# pimotor.net
KiCad netlist of a schematic drawn in EAGLE
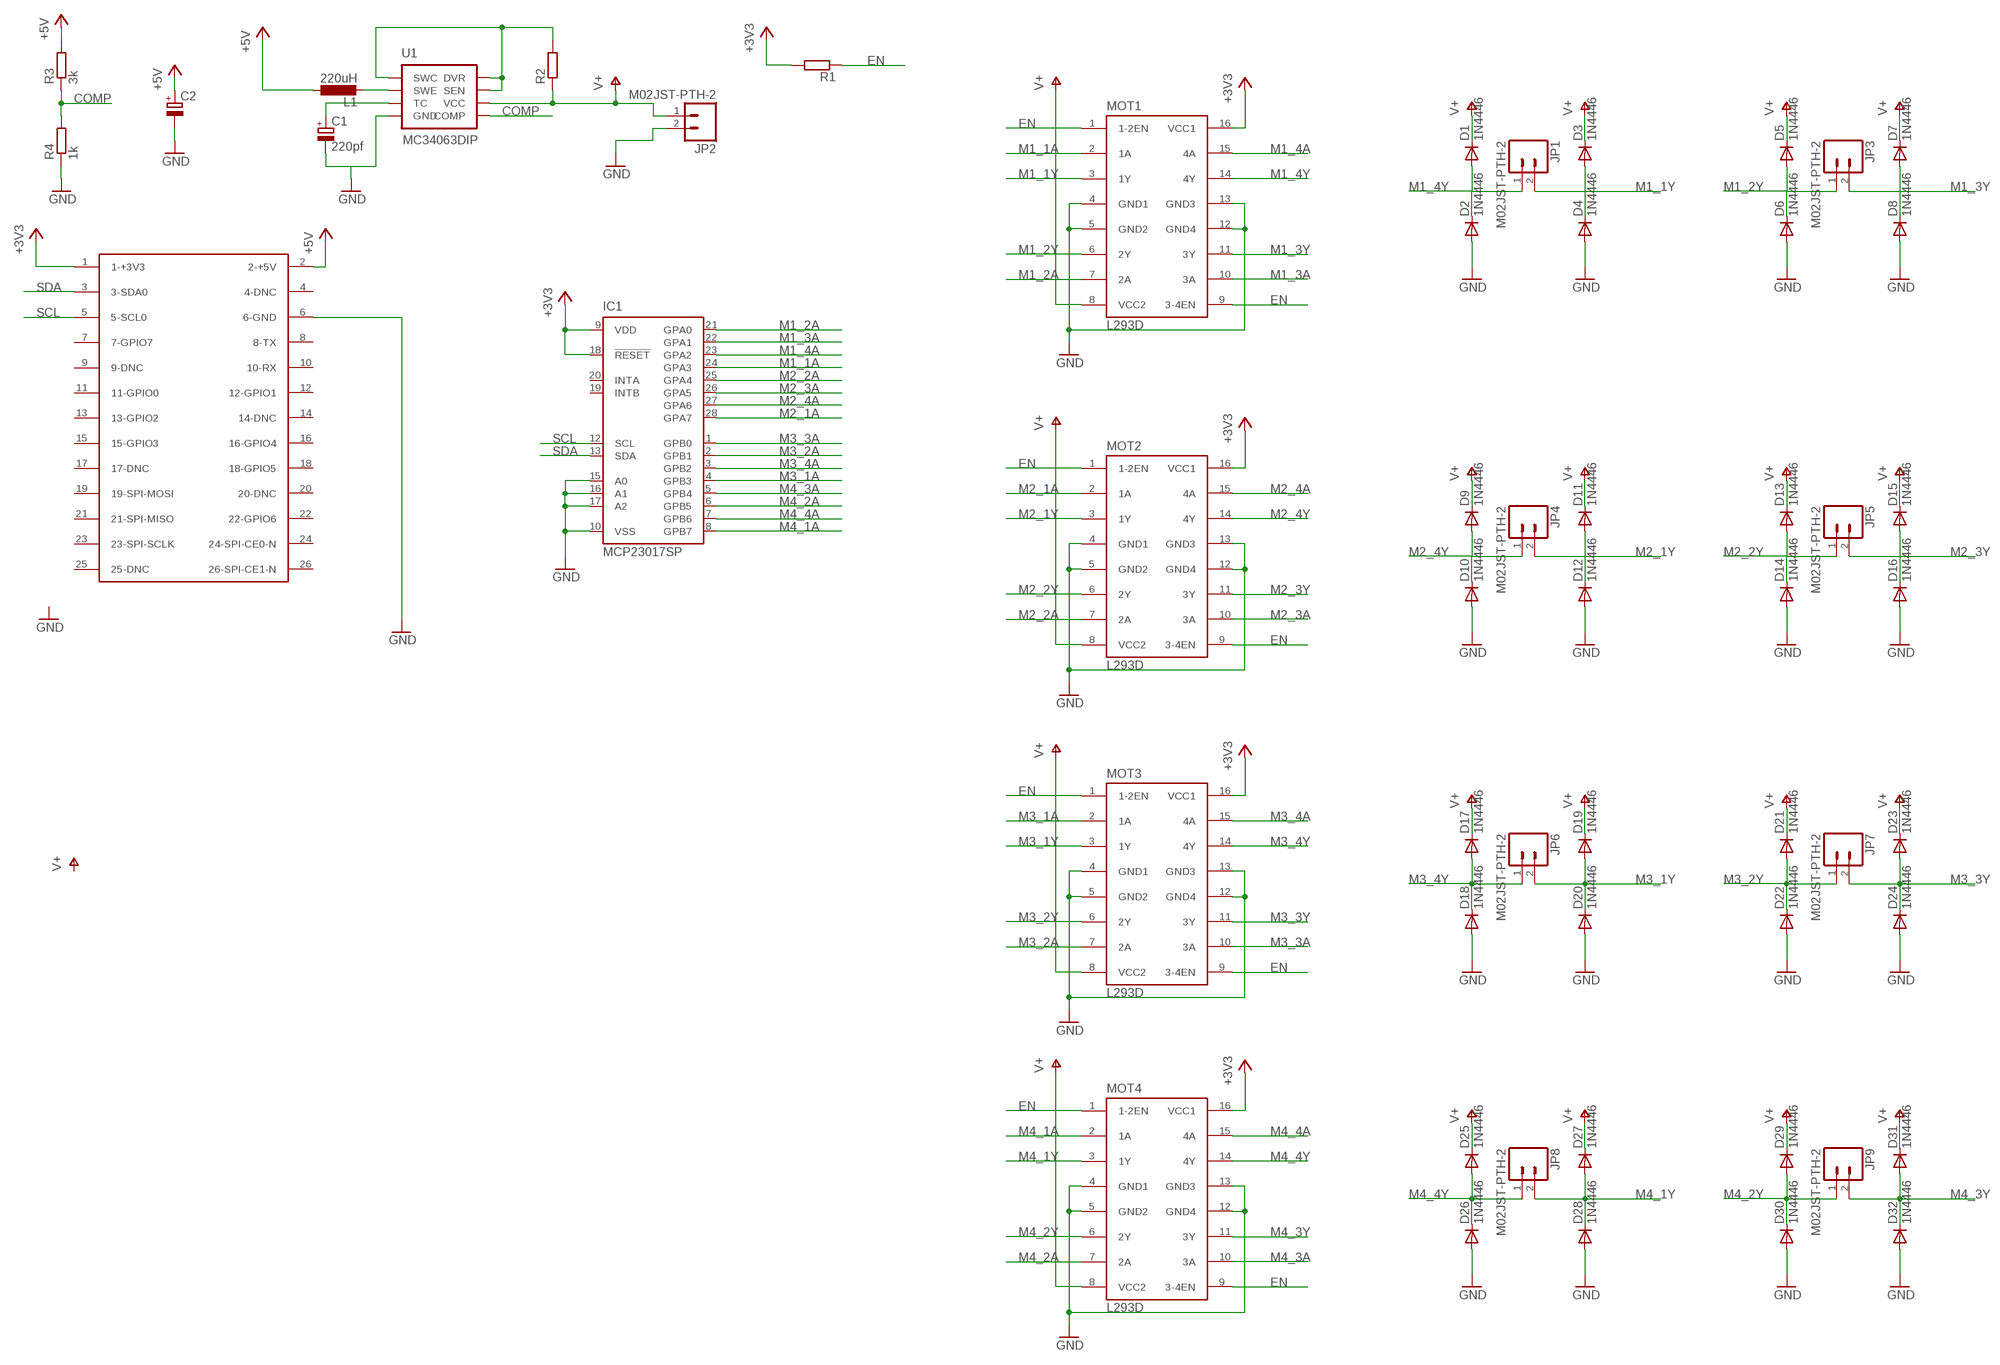
[diagram p0: schematic, sheet 1]

(export (version "E")
  (design (tool "Eeschema 10.0.6"))
  (components
    (comp (ref "C1")
      (value "220pf")
      (footprint "eagle-import:E3,5-8")
      (libsource (lib "eagle-import") (part "CPOL-EUE3.5-8"))
    )
    (comp (ref "C2")
      (value "CPOL-EUE3.5-8")
      (footprint "eagle-import:E3,5-8")
      (libsource (lib "eagle-import") (part "CPOL-EUE3.5-8"))
    )
    (comp (ref "D1")
      (value "1N4446")
      (footprint "eagle-import:DO35-10")
      (libsource (lib "eagle-import") (part "1N4446"))
    )
    (comp (ref "D2")
      (value "1N4446")
      (footprint "eagle-import:DO35-10")
      (libsource (lib "eagle-import") (part "1N4446"))
    )
    (comp (ref "D3")
      (value "1N4446")
      (footprint "eagle-import:DO35-10")
      (libsource (lib "eagle-import") (part "1N4446"))
    )
    (comp (ref "D4")
      (value "1N4446")
      (footprint "eagle-import:DO35-10")
      (libsource (lib "eagle-import") (part "1N4446"))
    )
    (comp (ref "D5")
      (value "1N4446")
      (footprint "eagle-import:DO35-10")
      (libsource (lib "eagle-import") (part "1N4446"))
    )
    (comp (ref "D6")
      (value "1N4446")
      (footprint "eagle-import:DO35-10")
      (libsource (lib "eagle-import") (part "1N4446"))
    )
    (comp (ref "D7")
      (value "1N4446")
      (footprint "eagle-import:DO35-10")
      (libsource (lib "eagle-import") (part "1N4446"))
    )
    (comp (ref "D8")
      (value "1N4446")
      (footprint "eagle-import:DO35-10")
      (libsource (lib "eagle-import") (part "1N4446"))
    )
    (comp (ref "D9")
      (value "1N4446")
      (footprint "eagle-import:DO35-10")
      (libsource (lib "eagle-import") (part "1N4446"))
    )
    (comp (ref "D10")
      (value "1N4446")
      (footprint "eagle-import:DO35-10")
      (libsource (lib "eagle-import") (part "1N4446"))
    )
    (comp (ref "D11")
      (value "1N4446")
      (footprint "eagle-import:DO35-10")
      (libsource (lib "eagle-import") (part "1N4446"))
    )
    (comp (ref "D12")
      (value "1N4446")
      (footprint "eagle-import:DO35-10")
      (libsource (lib "eagle-import") (part "1N4446"))
    )
    (comp (ref "D13")
      (value "1N4446")
      (footprint "eagle-import:DO35-10")
      (libsource (lib "eagle-import") (part "1N4446"))
    )
    (comp (ref "D14")
      (value "1N4446")
      (footprint "eagle-import:DO35-10")
      (libsource (lib "eagle-import") (part "1N4446"))
    )
    (comp (ref "D15")
      (value "1N4446")
      (footprint "eagle-import:DO35-10")
      (libsource (lib "eagle-import") (part "1N4446"))
    )
    (comp (ref "D16")
      (value "1N4446")
      (footprint "eagle-import:DO35-10")
      (libsource (lib "eagle-import") (part "1N4446"))
    )
    (comp (ref "D17")
      (value "1N4446")
      (footprint "eagle-import:DO35-10")
      (libsource (lib "eagle-import") (part "1N4446"))
    )
    (comp (ref "D18")
      (value "1N4446")
      (footprint "eagle-import:DO35-10")
      (libsource (lib "eagle-import") (part "1N4446"))
    )
    (comp (ref "D19")
      (value "1N4446")
      (footprint "eagle-import:DO35-10")
      (libsource (lib "eagle-import") (part "1N4446"))
    )
    (comp (ref "D20")
      (value "1N4446")
      (footprint "eagle-import:DO35-10")
      (libsource (lib "eagle-import") (part "1N4446"))
    )
    (comp (ref "D21")
      (value "1N4446")
      (footprint "eagle-import:DO35-10")
      (libsource (lib "eagle-import") (part "1N4446"))
    )
    (comp (ref "D22")
      (value "1N4446")
      (footprint "eagle-import:DO35-10")
      (libsource (lib "eagle-import") (part "1N4446"))
    )
    (comp (ref "D23")
      (value "1N4446")
      (footprint "eagle-import:DO35-10")
      (libsource (lib "eagle-import") (part "1N4446"))
    )
    (comp (ref "D24")
      (value "1N4446")
      (footprint "eagle-import:DO35-10")
      (libsource (lib "eagle-import") (part "1N4446"))
    )
    (comp (ref "D25")
      (value "1N4446")
      (footprint "eagle-import:DO35-10")
      (libsource (lib "eagle-import") (part "1N4446"))
    )
    (comp (ref "D26")
      (value "1N4446")
      (footprint "eagle-import:DO35-10")
      (libsource (lib "eagle-import") (part "1N4446"))
    )
    (comp (ref "D27")
      (value "1N4446")
      (footprint "eagle-import:DO35-10")
      (libsource (lib "eagle-import") (part "1N4446"))
    )
    (comp (ref "D28")
      (value "1N4446")
      (footprint "eagle-import:DO35-10")
      (libsource (lib "eagle-import") (part "1N4446"))
    )
    (comp (ref "D29")
      (value "1N4446")
      (footprint "eagle-import:DO35-10")
      (libsource (lib "eagle-import") (part "1N4446"))
    )
    (comp (ref "D30")
      (value "1N4446")
      (footprint "eagle-import:DO35-10")
      (libsource (lib "eagle-import") (part "1N4446"))
    )
    (comp (ref "D31")
      (value "1N4446")
      (footprint "eagle-import:DO35-10")
      (libsource (lib "eagle-import") (part "1N4446"))
    )
    (comp (ref "D32")
      (value "1N4446")
      (footprint "eagle-import:DO35-10")
      (libsource (lib "eagle-import") (part "1N4446"))
    )
    (comp (ref "IC1")
      (value "MCP23017SP")
      (footprint "eagle-import:DIL28-3")
      (libsource (lib "eagle-import") (part "MCP23017SP"))
    )
    (comp (ref "JP1")
      (value "M02JST-PTH-2")
      (footprint "eagle-import:JST-2-PTH")
      (libsource (lib "eagle-import") (part "M02JST-PTH-2"))
    )
    (comp (ref "JP2")
      (value "M02JST-PTH-2")
      (footprint "eagle-import:JST-2-PTH")
      (libsource (lib "eagle-import") (part "M02JST-PTH-2"))
    )
    (comp (ref "JP3")
      (value "M02JST-PTH-2")
      (footprint "eagle-import:JST-2-PTH")
      (libsource (lib "eagle-import") (part "M02JST-PTH-2"))
    )
    (comp (ref "JP4")
      (value "M02JST-PTH-2")
      (footprint "eagle-import:JST-2-PTH")
      (libsource (lib "eagle-import") (part "M02JST-PTH-2"))
    )
    (comp (ref "JP5")
      (value "M02JST-PTH-2")
      (footprint "eagle-import:JST-2-PTH")
      (libsource (lib "eagle-import") (part "M02JST-PTH-2"))
    )
    (comp (ref "JP6")
      (value "M02JST-PTH-2")
      (footprint "eagle-import:JST-2-PTH")
      (libsource (lib "eagle-import") (part "M02JST-PTH-2"))
    )
    (comp (ref "JP7")
      (value "M02JST-PTH-2")
      (footprint "eagle-import:JST-2-PTH")
      (libsource (lib "eagle-import") (part "M02JST-PTH-2"))
    )
    (comp (ref "JP8")
      (value "M02JST-PTH-2")
      (footprint "eagle-import:JST-2-PTH")
      (libsource (lib "eagle-import") (part "M02JST-PTH-2"))
    )
    (comp (ref "JP9")
      (value "M02JST-PTH-2")
      (footprint "eagle-import:JST-2-PTH")
      (libsource (lib "eagle-import") (part "M02JST-PTH-2"))
    )
    (comp (ref "L1")
      (value "220uH")
      (footprint "eagle-import:0204_7")
      (libsource (lib "eagle-import") (part "L-EU0204/7"))
    )
    (comp (ref "MOT1")
      (value "L293D")
      (footprint "eagle-import:DIL16")
      (libsource (lib "eagle-import") (part "L293D"))
    )
    (comp (ref "MOT2")
      (value "L293D")
      (footprint "eagle-import:DIL16")
      (libsource (lib "eagle-import") (part "L293D"))
    )
    (comp (ref "MOT3")
      (value "L293D")
      (footprint "eagle-import:DIL16")
      (libsource (lib "eagle-import") (part "L293D"))
    )
    (comp (ref "MOT4")
      (value "L293D")
      (footprint "eagle-import:DIL16")
      (libsource (lib "eagle-import") (part "L293D"))
    )
    (comp (ref "R1")
      (value "R-EU_0204/7")
      (footprint "eagle-import:0204_7")
      (libsource (lib "eagle-import") (part "R-EU_0204/7"))
    )
    (comp (ref "R2")
      (value "R-EU_0204/7")
      (footprint "eagle-import:0204_7")
      (libsource (lib "eagle-import") (part "R-EU_0204/7"))
    )
    (comp (ref "R3")
      (value "3k")
      (footprint "eagle-import:0204_7")
      (libsource (lib "eagle-import") (part "R-EU_0204/7"))
    )
    (comp (ref "R4")
      (value "1k")
      (footprint "eagle-import:0204_7")
      (libsource (lib "eagle-import") (part "R-EU_0204/7"))
    )
    (comp (ref "U$1")
      (value "RASPBERRY-PI")
      (footprint "eagle-import:RASPBERRY-PI")
      (libsource (lib "eagle-import") (part "RASPBERRY-PI"))
    )
    (comp (ref "U1")
      (value "MC34063DIP")
      (footprint "eagle-import:DIP-08")
      (libsource (lib "eagle-import") (part "MC34063DIP"))
    )
  )
  (nets
    (net (code "1") (name "+3V3") (class "Default")
      (node (ref "IC1") (pin "18") (pinfunction "~{RESET}_18") (pintype "input"))
      (node (ref "IC1") (pin "9") (pinfunction "VDD_9") (pintype "power_in"))
      (node (ref "MOT1") (pin "16") (pinfunction "VCC1_16") (pintype "power_in"))
      (node (ref "MOT2") (pin "16") (pinfunction "VCC1_16") (pintype "power_in"))
      (node (ref "MOT3") (pin "16") (pinfunction "VCC1_16") (pintype "power_in"))
      (node (ref "MOT4") (pin "16") (pinfunction "VCC1_16") (pintype "power_in"))
      (node (ref "R1") (pin "2") (pinfunction "2_2") (pintype "passive"))
      (node (ref "U$1") (pin "1") (pinfunction "1-+3V3_1") (pintype "bidirectional"))
    )
    (net (code "2") (name "+5V") (class "Default")
      (node (ref "C2") (pin "+") (pinfunction "+_+") (pintype "passive"))
      (node (ref "L1") (pin "1") (pinfunction "1_1") (pintype "passive"))
      (node (ref "R3") (pin "2") (pinfunction "2_2") (pintype "passive"))
      (node (ref "U$1") (pin "2") (pinfunction "2-+5V_2") (pintype "bidirectional"))
    )
    (net (code "3") (name "/COMP") (class "Default")
      (node (ref "R3") (pin "1") (pinfunction "1_1") (pintype "passive"))
      (node (ref "R4") (pin "2") (pinfunction "2_2") (pintype "passive"))
      (node (ref "U1") (pin "5") (pinfunction "COMP_5") (pintype "bidirectional"))
    )
    (net (code "4") (name "/EN") (class "Default")
      (node (ref "MOT1") (pin "1") (pinfunction "1-2EN_1") (pintype "input"))
      (node (ref "MOT1") (pin "9") (pinfunction "3-4EN_9") (pintype "input"))
      (node (ref "MOT2") (pin "1") (pinfunction "1-2EN_1") (pintype "input"))
      (node (ref "MOT2") (pin "9") (pinfunction "3-4EN_9") (pintype "input"))
      (node (ref "MOT3") (pin "1") (pinfunction "1-2EN_1") (pintype "input"))
      (node (ref "MOT3") (pin "9") (pinfunction "3-4EN_9") (pintype "input"))
      (node (ref "MOT4") (pin "1") (pinfunction "1-2EN_1") (pintype "input"))
      (node (ref "MOT4") (pin "9") (pinfunction "3-4EN_9") (pintype "input"))
      (node (ref "R1") (pin "1") (pinfunction "1_1") (pintype "passive"))
    )
    (net (code "5") (name "/M1_1A") (class "Default")
      (node (ref "IC1") (pin "24") (pinfunction "GPA3_24") (pintype "bidirectional"))
      (node (ref "MOT1") (pin "2") (pinfunction "1A_2") (pintype "input"))
    )
    (net (code "6") (name "/M1_1Y") (class "Default")
      (node (ref "D3") (pin "A") (pinfunction "A_A") (pintype "passive"))
      (node (ref "D4") (pin "C") (pinfunction "C_C") (pintype "passive"))
      (node (ref "JP1") (pin "2") (pinfunction "2_2") (pintype "passive"))
      (node (ref "MOT1") (pin "3") (pinfunction "1Y_3") (pintype "output"))
    )
    (net (code "7") (name "/M1_2A") (class "Default")
      (node (ref "IC1") (pin "21") (pinfunction "GPA0_21") (pintype "bidirectional"))
      (node (ref "MOT1") (pin "7") (pinfunction "2A_7") (pintype "input"))
    )
    (net (code "8") (name "/M1_2Y") (class "Default")
      (node (ref "D5") (pin "A") (pinfunction "A_A") (pintype "passive"))
      (node (ref "D6") (pin "C") (pinfunction "C_C") (pintype "passive"))
      (node (ref "JP3") (pin "1") (pinfunction "1_1") (pintype "passive"))
      (node (ref "MOT1") (pin "6") (pinfunction "2Y_6") (pintype "output"))
    )
    (net (code "9") (name "/M1_3A") (class "Default")
      (node (ref "IC1") (pin "22") (pinfunction "GPA1_22") (pintype "bidirectional"))
      (node (ref "MOT1") (pin "10") (pinfunction "3A_10") (pintype "input"))
    )
    (net (code "10") (name "/M1_3Y") (class "Default")
      (node (ref "D7") (pin "A") (pinfunction "A_A") (pintype "passive"))
      (node (ref "D8") (pin "C") (pinfunction "C_C") (pintype "passive"))
      (node (ref "JP3") (pin "2") (pinfunction "2_2") (pintype "passive"))
      (node (ref "MOT1") (pin "11") (pinfunction "3Y_11") (pintype "output"))
    )
    (net (code "11") (name "/M1_4A") (class "Default")
      (node (ref "IC1") (pin "23") (pinfunction "GPA2_23") (pintype "bidirectional"))
      (node (ref "MOT1") (pin "15") (pinfunction "4A_15") (pintype "input"))
    )
    (net (code "12") (name "/M1_4Y") (class "Default")
      (node (ref "D1") (pin "A") (pinfunction "A_A") (pintype "passive"))
      (node (ref "D2") (pin "C") (pinfunction "C_C") (pintype "passive"))
      (node (ref "JP1") (pin "1") (pinfunction "1_1") (pintype "passive"))
      (node (ref "MOT1") (pin "14") (pinfunction "4Y_14") (pintype "output"))
    )
    (net (code "13") (name "/M2_1A") (class "Default")
      (node (ref "IC1") (pin "28") (pinfunction "GPA7_28") (pintype "bidirectional"))
      (node (ref "MOT2") (pin "2") (pinfunction "1A_2") (pintype "input"))
    )
    (net (code "14") (name "/M2_1Y") (class "Default")
      (node (ref "D11") (pin "A") (pinfunction "A_A") (pintype "passive"))
      (node (ref "D12") (pin "C") (pinfunction "C_C") (pintype "passive"))
      (node (ref "JP4") (pin "2") (pinfunction "2_2") (pintype "passive"))
      (node (ref "MOT2") (pin "3") (pinfunction "1Y_3") (pintype "output"))
    )
    (net (code "15") (name "/M2_2A") (class "Default")
      (node (ref "IC1") (pin "25") (pinfunction "GPA4_25") (pintype "bidirectional"))
      (node (ref "MOT2") (pin "7") (pinfunction "2A_7") (pintype "input"))
    )
    (net (code "16") (name "/M2_2Y") (class "Default")
      (node (ref "D13") (pin "A") (pinfunction "A_A") (pintype "passive"))
      (node (ref "D14") (pin "C") (pinfunction "C_C") (pintype "passive"))
      (node (ref "JP5") (pin "1") (pinfunction "1_1") (pintype "passive"))
      (node (ref "MOT2") (pin "6") (pinfunction "2Y_6") (pintype "output"))
    )
    (net (code "17") (name "/M2_3A") (class "Default")
      (node (ref "IC1") (pin "26") (pinfunction "GPA5_26") (pintype "bidirectional"))
      (node (ref "MOT2") (pin "10") (pinfunction "3A_10") (pintype "input"))
    )
    (net (code "18") (name "/M2_3Y") (class "Default")
      (node (ref "D15") (pin "A") (pinfunction "A_A") (pintype "passive"))
      (node (ref "D16") (pin "C") (pinfunction "C_C") (pintype "passive"))
      (node (ref "JP5") (pin "2") (pinfunction "2_2") (pintype "passive"))
      (node (ref "MOT2") (pin "11") (pinfunction "3Y_11") (pintype "output"))
    )
    (net (code "19") (name "/M2_4A") (class "Default")
      (node (ref "IC1") (pin "27") (pinfunction "GPA6_27") (pintype "bidirectional"))
      (node (ref "MOT2") (pin "15") (pinfunction "4A_15") (pintype "input"))
    )
    (net (code "20") (name "/M2_4Y") (class "Default")
      (node (ref "D10") (pin "C") (pinfunction "C_C") (pintype "passive"))
      (node (ref "D9") (pin "A") (pinfunction "A_A") (pintype "passive"))
      (node (ref "JP4") (pin "1") (pinfunction "1_1") (pintype "passive"))
      (node (ref "MOT2") (pin "14") (pinfunction "4Y_14") (pintype "output"))
    )
    (net (code "21") (name "/M3_1A") (class "Default")
      (node (ref "IC1") (pin "4") (pinfunction "GPB3_4") (pintype "bidirectional"))
      (node (ref "MOT3") (pin "2") (pinfunction "1A_2") (pintype "input"))
    )
    (net (code "22") (name "/M3_1Y") (class "Default")
      (node (ref "D19") (pin "A") (pinfunction "A_A") (pintype "passive"))
      (node (ref "D20") (pin "C") (pinfunction "C_C") (pintype "passive"))
      (node (ref "JP6") (pin "2") (pinfunction "2_2") (pintype "passive"))
      (node (ref "MOT3") (pin "3") (pinfunction "1Y_3") (pintype "output"))
    )
    (net (code "23") (name "/M3_2A") (class "Default")
      (node (ref "IC1") (pin "2") (pinfunction "GPB1_2") (pintype "bidirectional"))
      (node (ref "MOT3") (pin "7") (pinfunction "2A_7") (pintype "input"))
    )
    (net (code "24") (name "/M3_2Y") (class "Default")
      (node (ref "D21") (pin "A") (pinfunction "A_A") (pintype "passive"))
      (node (ref "D22") (pin "C") (pinfunction "C_C") (pintype "passive"))
      (node (ref "JP7") (pin "1") (pinfunction "1_1") (pintype "passive"))
      (node (ref "MOT3") (pin "6") (pinfunction "2Y_6") (pintype "output"))
    )
    (net (code "25") (name "/M3_3A") (class "Default")
      (node (ref "IC1") (pin "1") (pinfunction "GPB0_1") (pintype "bidirectional"))
      (node (ref "MOT3") (pin "10") (pinfunction "3A_10") (pintype "input"))
    )
    (net (code "26") (name "/M3_3Y") (class "Default")
      (node (ref "D23") (pin "A") (pinfunction "A_A") (pintype "passive"))
      (node (ref "D24") (pin "C") (pinfunction "C_C") (pintype "passive"))
      (node (ref "JP7") (pin "2") (pinfunction "2_2") (pintype "passive"))
      (node (ref "MOT3") (pin "11") (pinfunction "3Y_11") (pintype "output"))
    )
    (net (code "27") (name "/M3_4A") (class "Default")
      (node (ref "IC1") (pin "3") (pinfunction "GPB2_3") (pintype "bidirectional"))
      (node (ref "MOT3") (pin "15") (pinfunction "4A_15") (pintype "input"))
    )
    (net (code "28") (name "/M3_4Y") (class "Default")
      (node (ref "D17") (pin "A") (pinfunction "A_A") (pintype "passive"))
      (node (ref "D18") (pin "C") (pinfunction "C_C") (pintype "passive"))
      (node (ref "JP6") (pin "1") (pinfunction "1_1") (pintype "passive"))
      (node (ref "MOT3") (pin "14") (pinfunction "4Y_14") (pintype "output"))
    )
    (net (code "29") (name "/M4_1A") (class "Default")
      (node (ref "IC1") (pin "8") (pinfunction "GPB7_8") (pintype "bidirectional"))
      (node (ref "MOT4") (pin "2") (pinfunction "1A_2") (pintype "input"))
    )
    (net (code "30") (name "/M4_1Y") (class "Default")
      (node (ref "D27") (pin "A") (pinfunction "A_A") (pintype "passive"))
      (node (ref "D28") (pin "C") (pinfunction "C_C") (pintype "passive"))
      (node (ref "JP8") (pin "2") (pinfunction "2_2") (pintype "passive"))
      (node (ref "MOT4") (pin "3") (pinfunction "1Y_3") (pintype "output"))
    )
    (net (code "31") (name "/M4_2A") (class "Default")
      (node (ref "IC1") (pin "6") (pinfunction "GPB5_6") (pintype "bidirectional"))
      (node (ref "MOT4") (pin "7") (pinfunction "2A_7") (pintype "input"))
    )
    (net (code "32") (name "/M4_2Y") (class "Default")
      (node (ref "D29") (pin "A") (pinfunction "A_A") (pintype "passive"))
      (node (ref "D30") (pin "C") (pinfunction "C_C") (pintype "passive"))
      (node (ref "JP9") (pin "1") (pinfunction "1_1") (pintype "passive"))
      (node (ref "MOT4") (pin "6") (pinfunction "2Y_6") (pintype "output"))
    )
    (net (code "33") (name "/M4_3A") (class "Default")
      (node (ref "IC1") (pin "5") (pinfunction "GPB4_5") (pintype "bidirectional"))
      (node (ref "MOT4") (pin "10") (pinfunction "3A_10") (pintype "input"))
    )
    (net (code "34") (name "/M4_3Y") (class "Default")
      (node (ref "D31") (pin "A") (pinfunction "A_A") (pintype "passive"))
      (node (ref "D32") (pin "C") (pinfunction "C_C") (pintype "passive"))
      (node (ref "JP9") (pin "2") (pinfunction "2_2") (pintype "passive"))
      (node (ref "MOT4") (pin "11") (pinfunction "3Y_11") (pintype "output"))
    )
    (net (code "35") (name "/M4_4A") (class "Default")
      (node (ref "IC1") (pin "7") (pinfunction "GPB6_7") (pintype "bidirectional"))
      (node (ref "MOT4") (pin "15") (pinfunction "4A_15") (pintype "input"))
    )
    (net (code "36") (name "/M4_4Y") (class "Default")
      (node (ref "D25") (pin "A") (pinfunction "A_A") (pintype "passive"))
      (node (ref "D26") (pin "C") (pinfunction "C_C") (pintype "passive"))
      (node (ref "JP8") (pin "1") (pinfunction "1_1") (pintype "passive"))
      (node (ref "MOT4") (pin "14") (pinfunction "4Y_14") (pintype "output"))
    )
    (net (code "37") (name "/SCL") (class "Default")
      (node (ref "IC1") (pin "12") (pinfunction "SCL_12") (pintype "input"))
      (node (ref "U$1") (pin "5") (pinfunction "5-SCL0_5") (pintype "bidirectional"))
    )
    (net (code "38") (name "/SDA") (class "Default")
      (node (ref "IC1") (pin "13") (pinfunction "SDA_13") (pintype "bidirectional"))
      (node (ref "U$1") (pin "3") (pinfunction "3-SDA0_3") (pintype "bidirectional"))
    )
    (net (code "39") (name "GND") (class "Default")
      (node (ref "C1") (pin "-") (pinfunction "-_-") (pintype "passive"))
      (node (ref "C2") (pin "-") (pinfunction "-_-") (pintype "passive"))
      (node (ref "D10") (pin "A") (pinfunction "A_A") (pintype "passive"))
      (node (ref "D12") (pin "A") (pinfunction "A_A") (pintype "passive"))
      (node (ref "D14") (pin "A") (pinfunction "A_A") (pintype "passive"))
      (node (ref "D16") (pin "A") (pinfunction "A_A") (pintype "passive"))
      (node (ref "D18") (pin "A") (pinfunction "A_A") (pintype "passive"))
      (node (ref "D2") (pin "A") (pinfunction "A_A") (pintype "passive"))
      (node (ref "D20") (pin "A") (pinfunction "A_A") (pintype "passive"))
      (node (ref "D22") (pin "A") (pinfunction "A_A") (pintype "passive"))
      (node (ref "D24") (pin "A") (pinfunction "A_A") (pintype "passive"))
      (node (ref "D26") (pin "A") (pinfunction "A_A") (pintype "passive"))
      (node (ref "D28") (pin "A") (pinfunction "A_A") (pintype "passive"))
      (node (ref "D30") (pin "A") (pinfunction "A_A") (pintype "passive"))
      (node (ref "D32") (pin "A") (pinfunction "A_A") (pintype "passive"))
      (node (ref "D4") (pin "A") (pinfunction "A_A") (pintype "passive"))
      (node (ref "D6") (pin "A") (pinfunction "A_A") (pintype "passive"))
      (node (ref "D8") (pin "A") (pinfunction "A_A") (pintype "passive"))
      (node (ref "IC1") (pin "10") (pinfunction "VSS_10") (pintype "power_in"))
      (node (ref "IC1") (pin "15") (pinfunction "A0_15") (pintype "input"))
      (node (ref "IC1") (pin "16") (pinfunction "A1_16") (pintype "input"))
      (node (ref "IC1") (pin "17") (pinfunction "A2_17") (pintype "input"))
      (node (ref "JP2") (pin "2") (pinfunction "2_2") (pintype "passive"))
      (node (ref "MOT1") (pin "12") (pinfunction "GND4_12") (pintype "power_in"))
      (node (ref "MOT1") (pin "13") (pinfunction "GND3_13") (pintype "power_in"))
      (node (ref "MOT1") (pin "4") (pinfunction "GND1_4") (pintype "power_in"))
      (node (ref "MOT1") (pin "5") (pinfunction "GND2_5") (pintype "power_in"))
      (node (ref "MOT2") (pin "12") (pinfunction "GND4_12") (pintype "power_in"))
      (node (ref "MOT2") (pin "13") (pinfunction "GND3_13") (pintype "power_in"))
      (node (ref "MOT2") (pin "4") (pinfunction "GND1_4") (pintype "power_in"))
      (node (ref "MOT2") (pin "5") (pinfunction "GND2_5") (pintype "power_in"))
      (node (ref "MOT3") (pin "12") (pinfunction "GND4_12") (pintype "power_in"))
      (node (ref "MOT3") (pin "13") (pinfunction "GND3_13") (pintype "power_in"))
      (node (ref "MOT3") (pin "4") (pinfunction "GND1_4") (pintype "power_in"))
      (node (ref "MOT3") (pin "5") (pinfunction "GND2_5") (pintype "power_in"))
      (node (ref "MOT4") (pin "12") (pinfunction "GND4_12") (pintype "power_in"))
      (node (ref "MOT4") (pin "13") (pinfunction "GND3_13") (pintype "power_in"))
      (node (ref "MOT4") (pin "4") (pinfunction "GND1_4") (pintype "power_in"))
      (node (ref "MOT4") (pin "5") (pinfunction "GND2_5") (pintype "power_in"))
      (node (ref "R4") (pin "1") (pinfunction "1_1") (pintype "passive"))
      (node (ref "U$1") (pin "6") (pinfunction "6-GND_6") (pintype "bidirectional"))
      (node (ref "U1") (pin "4") (pinfunction "GND_4") (pintype "bidirectional"))
    )
    (net (code "40") (name "Net-(U1-DVR)") (class "Default")
      (node (ref "R2") (pin "2") (pinfunction "2_2") (pintype "passive"))
      (node (ref "U1") (pin "1") (pinfunction "SWC_1") (pintype "bidirectional"))
      (node (ref "U1") (pin "7") (pinfunction "SEN_7") (pintype "bidirectional"))
      (node (ref "U1") (pin "8") (pinfunction "DVR_8") (pintype "bidirectional"))
    )
    (net (code "41") (name "Net-(U1-SWE)") (class "Default")
      (node (ref "L1") (pin "2") (pinfunction "2_2") (pintype "passive"))
      (node (ref "U1") (pin "2") (pinfunction "SWE_2") (pintype "bidirectional"))
    )
    (net (code "42") (name "Net-(U1-TC)") (class "Default")
      (node (ref "C1") (pin "+") (pinfunction "+_+") (pintype "passive"))
      (node (ref "U1") (pin "3") (pinfunction "TC_3") (pintype "bidirectional"))
    )
    (net (code "43") (name "V+") (class "Default")
      (node (ref "D1") (pin "C") (pinfunction "C_C") (pintype "passive"))
      (node (ref "D11") (pin "C") (pinfunction "C_C") (pintype "passive"))
      (node (ref "D13") (pin "C") (pinfunction "C_C") (pintype "passive"))
      (node (ref "D15") (pin "C") (pinfunction "C_C") (pintype "passive"))
      (node (ref "D17") (pin "C") (pinfunction "C_C") (pintype "passive"))
      (node (ref "D19") (pin "C") (pinfunction "C_C") (pintype "passive"))
      (node (ref "D21") (pin "C") (pinfunction "C_C") (pintype "passive"))
      (node (ref "D23") (pin "C") (pinfunction "C_C") (pintype "passive"))
      (node (ref "D25") (pin "C") (pinfunction "C_C") (pintype "passive"))
      (node (ref "D27") (pin "C") (pinfunction "C_C") (pintype "passive"))
      (node (ref "D29") (pin "C") (pinfunction "C_C") (pintype "passive"))
      (node (ref "D3") (pin "C") (pinfunction "C_C") (pintype "passive"))
      (node (ref "D31") (pin "C") (pinfunction "C_C") (pintype "passive"))
      (node (ref "D5") (pin "C") (pinfunction "C_C") (pintype "passive"))
      (node (ref "D7") (pin "C") (pinfunction "C_C") (pintype "passive"))
      (node (ref "D9") (pin "C") (pinfunction "C_C") (pintype "passive"))
      (node (ref "JP2") (pin "1") (pinfunction "1_1") (pintype "passive"))
      (node (ref "MOT1") (pin "8") (pinfunction "VCC2_8") (pintype "power_in"))
      (node (ref "MOT2") (pin "8") (pinfunction "VCC2_8") (pintype "power_in"))
      (node (ref "MOT3") (pin "8") (pinfunction "VCC2_8") (pintype "power_in"))
      (node (ref "MOT4") (pin "8") (pinfunction "VCC2_8") (pintype "power_in"))
      (node (ref "R2") (pin "1") (pinfunction "1_1") (pintype "passive"))
      (node (ref "U1") (pin "6") (pinfunction "VCC_6") (pintype "bidirectional"))
    )
    (net (code "44") (name "unconnected-(IC1-INTA-Pad20)") (class "Default")
      (node (ref "IC1") (pin "20") (pinfunction "INTA_20") (pintype "output"))
    )
    (net (code "45") (name "unconnected-(IC1-INTB-Pad19)") (class "Default")
      (node (ref "IC1") (pin "19") (pinfunction "INTB_19") (pintype "output"))
    )
    (net (code "46") (name "unconnected-(U$1-4-DNC-Pad4)") (class "Default")
      (node (ref "U$1") (pin "4") (pinfunction "4-DNC_4") (pintype "bidirectional"))
    )
    (net (code "47") (name "unconnected-(U$1-7-GPIO7-Pad7)") (class "Default")
      (node (ref "U$1") (pin "7") (pinfunction "7-GPIO7_7") (pintype "bidirectional"))
    )
    (net (code "48") (name "unconnected-(U$1-8-TX-Pad8)") (class "Default")
      (node (ref "U$1") (pin "8") (pinfunction "8-TX_8") (pintype "bidirectional"))
    )
    (net (code "49") (name "unconnected-(U$1-9-DNC-Pad9)") (class "Default")
      (node (ref "U$1") (pin "9") (pinfunction "9-DNC_9") (pintype "bidirectional"))
    )
    (net (code "50") (name "unconnected-(U$1-10-RX-Pad10)") (class "Default")
      (node (ref "U$1") (pin "10") (pinfunction "10-RX_10") (pintype "bidirectional"))
    )
    (net (code "51") (name "unconnected-(U$1-11-GPIO0-Pad11)") (class "Default")
      (node (ref "U$1") (pin "11") (pinfunction "11-GPIO0_11") (pintype "bidirectional"))
    )
    (net (code "52") (name "unconnected-(U$1-12-GPIO1-Pad12)") (class "Default")
      (node (ref "U$1") (pin "12") (pinfunction "12-GPIO1_12") (pintype "bidirectional"))
    )
    (net (code "53") (name "unconnected-(U$1-13-GPIO2-Pad13)") (class "Default")
      (node (ref "U$1") (pin "13") (pinfunction "13-GPIO2_13") (pintype "bidirectional"))
    )
    (net (code "54") (name "unconnected-(U$1-14-DNC-Pad14)") (class "Default")
      (node (ref "U$1") (pin "14") (pinfunction "14-DNC_14") (pintype "bidirectional"))
    )
    (net (code "55") (name "unconnected-(U$1-15-GPIO3-Pad15)") (class "Default")
      (node (ref "U$1") (pin "15") (pinfunction "15-GPIO3_15") (pintype "bidirectional"))
    )
    (net (code "56") (name "unconnected-(U$1-16-GPIO4-Pad16)") (class "Default")
      (node (ref "U$1") (pin "16") (pinfunction "16-GPIO4_16") (pintype "bidirectional"))
    )
    (net (code "57") (name "unconnected-(U$1-17-DNC-Pad17)") (class "Default")
      (node (ref "U$1") (pin "17") (pinfunction "17-DNC_17") (pintype "bidirectional"))
    )
    (net (code "58") (name "unconnected-(U$1-18-GPIO5-Pad18)") (class "Default")
      (node (ref "U$1") (pin "18") (pinfunction "18-GPIO5_18") (pintype "bidirectional"))
    )
    (net (code "59") (name "unconnected-(U$1-19-SPI-MOSI-Pad19)") (class "Default")
      (node (ref "U$1") (pin "19") (pinfunction "19-SPI-MOSI_19") (pintype "bidirectional"))
    )
    (net (code "60") (name "unconnected-(U$1-20-DNC-Pad20)") (class "Default")
      (node (ref "U$1") (pin "20") (pinfunction "20-DNC_20") (pintype "bidirectional"))
    )
    (net (code "61") (name "unconnected-(U$1-21-SPI-MISO-Pad21)") (class "Default")
      (node (ref "U$1") (pin "21") (pinfunction "21-SPI-MISO_21") (pintype "bidirectional"))
    )
    (net (code "62") (name "unconnected-(U$1-22-GPIO6-Pad22)") (class "Default")
      (node (ref "U$1") (pin "22") (pinfunction "22-GPIO6_22") (pintype "bidirectional"))
    )
    (net (code "63") (name "unconnected-(U$1-23-SPI-SCLK-Pad23)") (class "Default")
      (node (ref "U$1") (pin "23") (pinfunction "23-SPI-SCLK_23") (pintype "bidirectional"))
    )
    (net (code "64") (name "unconnected-(U$1-24-SPI-CE0-N-Pad24)") (class "Default")
      (node (ref "U$1") (pin "24") (pinfunction "24-SPI-CE0-N_24") (pintype "bidirectional"))
    )
    (net (code "65") (name "unconnected-(U$1-25-DNC-Pad25)") (class "Default")
      (node (ref "U$1") (pin "25") (pinfunction "25-DNC_25") (pintype "bidirectional"))
    )
    (net (code "66") (name "unconnected-(U$1-26-SPI-CE1-N-Pad26)") (class "Default")
      (node (ref "U$1") (pin "26") (pinfunction "26-SPI-CE1-N_26") (pintype "bidirectional"))
    )
  )
)
